# Line_Board.net
KiCad netlist of a schematic drawn in EAGLE
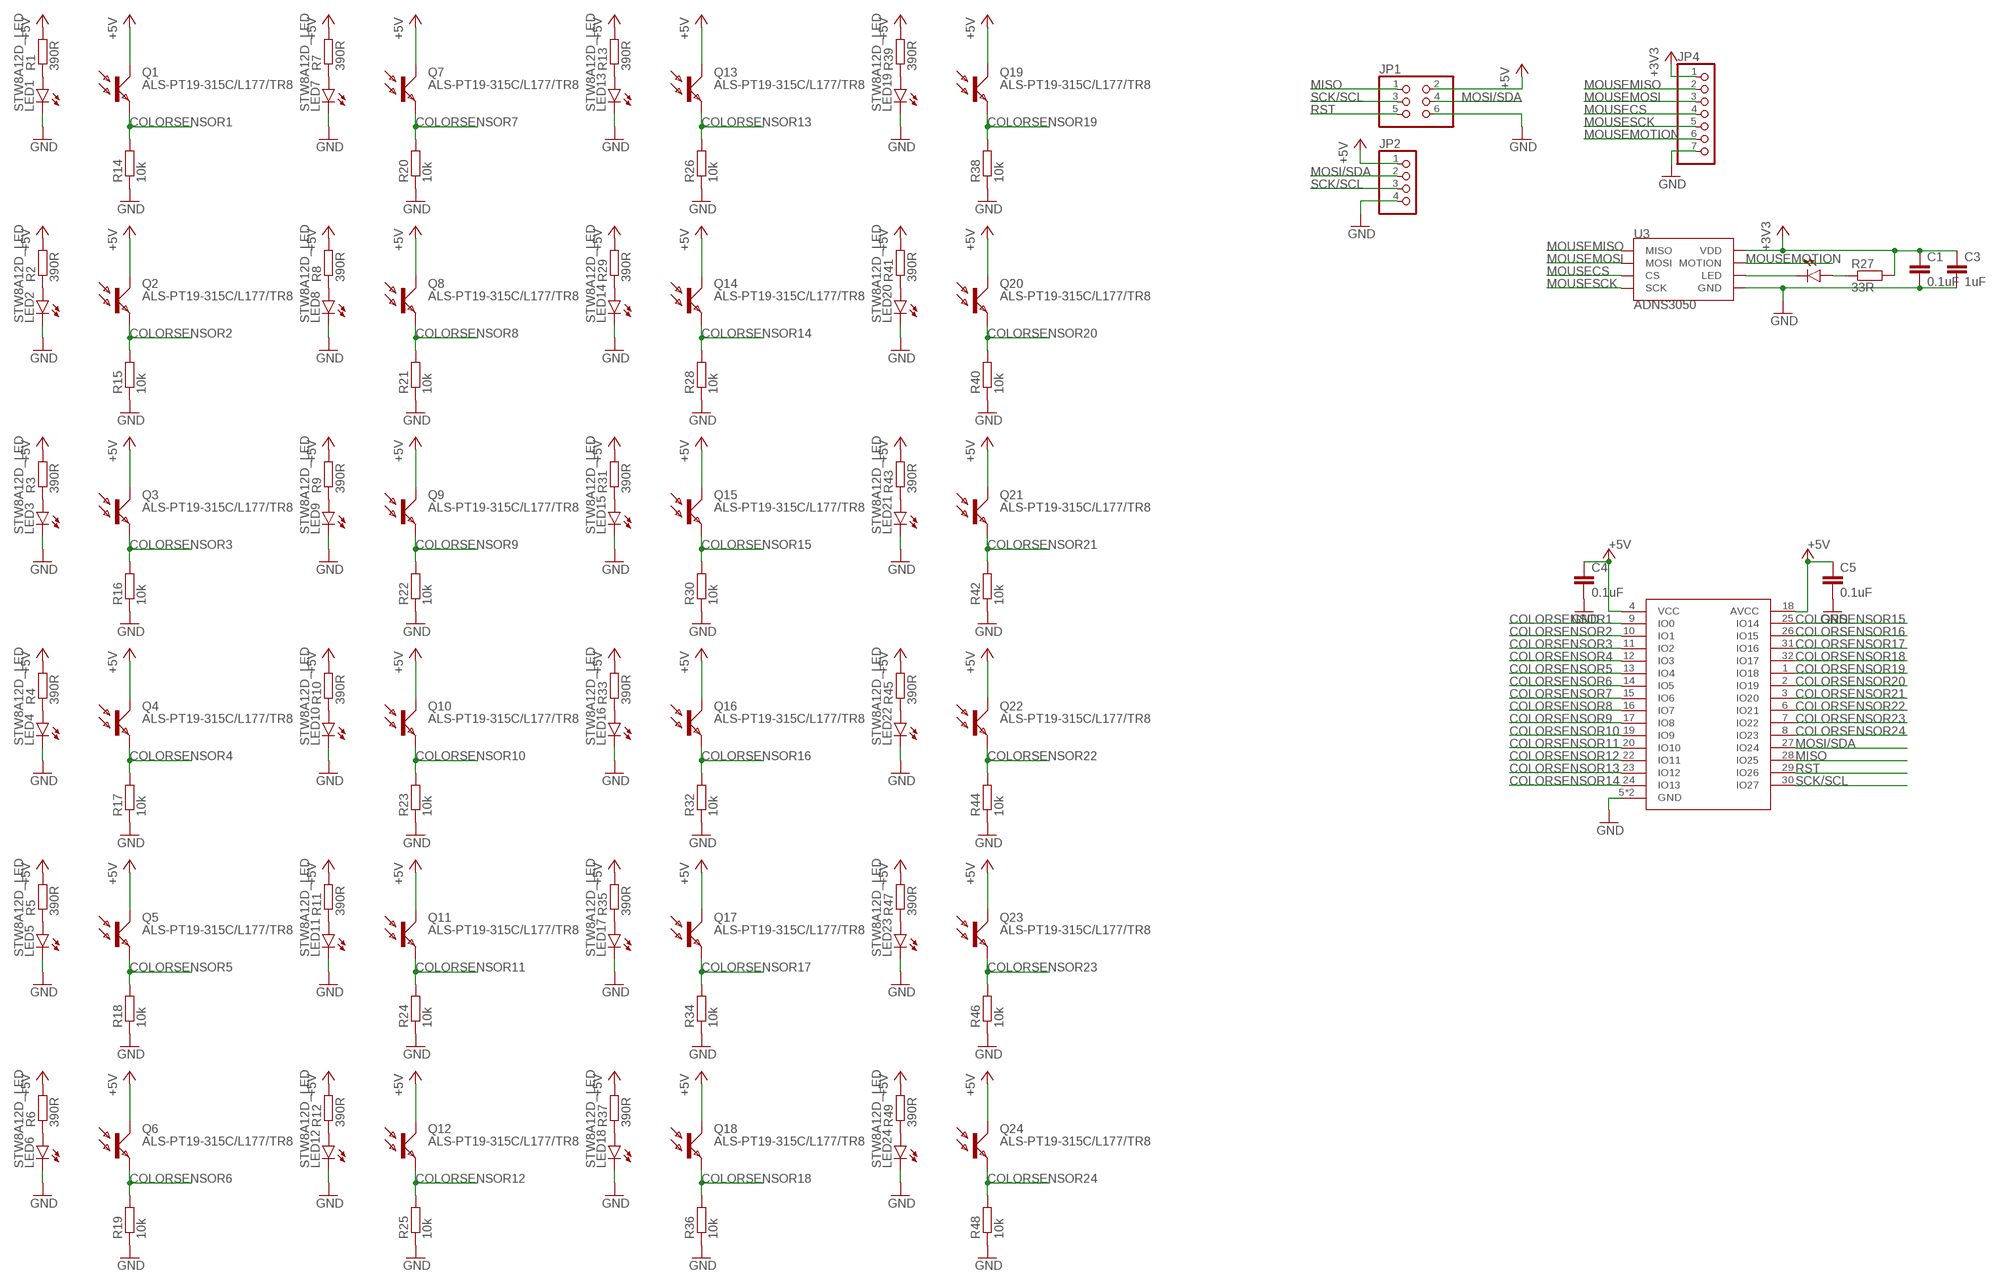
[diagram p0: schematic, sheet 1]

(export (version "E")
  (design (tool "Eeschema 10.0.6"))
  (components
    (comp (ref "C1")
      (value "0.1uF")
      (footprint "eagle-import:C0805")
      (libsource (lib "eagle-import") (part "C-EUC0805"))
    )
    (comp (ref "C3")
      (value "1uF")
      (footprint "eagle-import:C0805")
      (libsource (lib "eagle-import") (part "C-EUC0805"))
    )
    (comp (ref "C4")
      (value "0.1uF")
      (footprint "eagle-import:C0805")
      (libsource (lib "eagle-import") (part "C-EUC0805"))
    )
    (comp (ref "C5")
      (value "0.1uF")
      (footprint "eagle-import:C0805")
      (libsource (lib "eagle-import") (part "C-EUC0805"))
    )
    (comp (ref "JP1")
      (value "PINHD-2X3")
      (footprint "eagle-import:2X03")
      (libsource (lib "eagle-import") (part "PINHD-2X3"))
    )
    (comp (ref "JP2")
      (value "PINHD-1X4/90")
      (footprint "eagle-import:1X04_90")
      (libsource (lib "eagle-import") (part "PINHD-1X4/90"))
    )
    (comp (ref "JP4")
      (value "PINHD-1X7")
      (footprint "eagle-import:1X07")
      (libsource (lib "eagle-import") (part "PINHD-1X7"))
    )
    (comp (ref "LED1")
      (value "STW8A12D_LED")
      (footprint "eagle-import:LEDC3428X70")
      (libsource (lib "eagle-import") (part "STW8A12D_LED"))
    )
    (comp (ref "LED2")
      (value "STW8A12D_LED")
      (footprint "eagle-import:LEDC3428X70")
      (libsource (lib "eagle-import") (part "STW8A12D_LED"))
    )
    (comp (ref "LED3")
      (value "STW8A12D_LED")
      (footprint "eagle-import:LEDC3428X70")
      (libsource (lib "eagle-import") (part "STW8A12D_LED"))
    )
    (comp (ref "LED4")
      (value "STW8A12D_LED")
      (footprint "eagle-import:LEDC3428X70")
      (libsource (lib "eagle-import") (part "STW8A12D_LED"))
    )
    (comp (ref "LED5")
      (value "STW8A12D_LED")
      (footprint "eagle-import:LEDC3428X70")
      (libsource (lib "eagle-import") (part "STW8A12D_LED"))
    )
    (comp (ref "LED6")
      (value "STW8A12D_LED")
      (footprint "eagle-import:LEDC3428X70")
      (libsource (lib "eagle-import") (part "STW8A12D_LED"))
    )
    (comp (ref "LED7")
      (value "STW8A12D_LED")
      (footprint "eagle-import:LEDC3428X70")
      (libsource (lib "eagle-import") (part "STW8A12D_LED"))
    )
    (comp (ref "LED8")
      (value "STW8A12D_LED")
      (footprint "eagle-import:LEDC3428X70")
      (libsource (lib "eagle-import") (part "STW8A12D_LED"))
    )
    (comp (ref "LED9")
      (value "STW8A12D_LED")
      (footprint "eagle-import:LEDC3428X70")
      (libsource (lib "eagle-import") (part "STW8A12D_LED"))
    )
    (comp (ref "LED10")
      (value "STW8A12D_LED")
      (footprint "eagle-import:LEDC3428X70")
      (libsource (lib "eagle-import") (part "STW8A12D_LED"))
    )
    (comp (ref "LED11")
      (value "STW8A12D_LED")
      (footprint "eagle-import:LEDC3428X70")
      (libsource (lib "eagle-import") (part "STW8A12D_LED"))
    )
    (comp (ref "LED12")
      (value "STW8A12D_LED")
      (footprint "eagle-import:LEDC3428X70")
      (libsource (lib "eagle-import") (part "STW8A12D_LED"))
    )
    (comp (ref "LED13")
      (value "STW8A12D_LED")
      (footprint "eagle-import:LEDC3428X70")
      (libsource (lib "eagle-import") (part "STW8A12D_LED"))
    )
    (comp (ref "LED14")
      (value "STW8A12D_LED")
      (footprint "eagle-import:LEDC3428X70")
      (libsource (lib "eagle-import") (part "STW8A12D_LED"))
    )
    (comp (ref "LED15")
      (value "STW8A12D_LED")
      (footprint "eagle-import:LEDC3428X70")
      (libsource (lib "eagle-import") (part "STW8A12D_LED"))
    )
    (comp (ref "LED16")
      (value "STW8A12D_LED")
      (footprint "eagle-import:LEDC3428X70")
      (libsource (lib "eagle-import") (part "STW8A12D_LED"))
    )
    (comp (ref "LED17")
      (value "STW8A12D_LED")
      (footprint "eagle-import:LEDC3428X70")
      (libsource (lib "eagle-import") (part "STW8A12D_LED"))
    )
    (comp (ref "LED18")
      (value "STW8A12D_LED")
      (footprint "eagle-import:LEDC3428X70")
      (libsource (lib "eagle-import") (part "STW8A12D_LED"))
    )
    (comp (ref "LED19")
      (value "STW8A12D_LED")
      (footprint "eagle-import:LEDC3428X70")
      (libsource (lib "eagle-import") (part "STW8A12D_LED"))
    )
    (comp (ref "LED20")
      (value "STW8A12D_LED")
      (footprint "eagle-import:LEDC3428X70")
      (libsource (lib "eagle-import") (part "STW8A12D_LED"))
    )
    (comp (ref "LED21")
      (value "STW8A12D_LED")
      (footprint "eagle-import:LEDC3428X70")
      (libsource (lib "eagle-import") (part "STW8A12D_LED"))
    )
    (comp (ref "LED22")
      (value "STW8A12D_LED")
      (footprint "eagle-import:LEDC3428X70")
      (libsource (lib "eagle-import") (part "STW8A12D_LED"))
    )
    (comp (ref "LED23")
      (value "STW8A12D_LED")
      (footprint "eagle-import:LEDC3428X70")
      (libsource (lib "eagle-import") (part "STW8A12D_LED"))
    )
    (comp (ref "LED24")
      (value "STW8A12D_LED")
      (footprint "eagle-import:LEDC3428X70")
      (libsource (lib "eagle-import") (part "STW8A12D_LED"))
    )
    (comp (ref "Q1")
      (value "ALS-PT19-315C/L177/TR8")
      (footprint "eagle-import:LEDC1708X60")
      (libsource (lib "eagle-import") (part "ALS-PT19-315C/L177/TR8"))
    )
    (comp (ref "Q2")
      (value "ALS-PT19-315C/L177/TR8")
      (footprint "eagle-import:LEDC1708X60")
      (libsource (lib "eagle-import") (part "ALS-PT19-315C/L177/TR8"))
    )
    (comp (ref "Q3")
      (value "ALS-PT19-315C/L177/TR8")
      (footprint "eagle-import:LEDC1708X60")
      (libsource (lib "eagle-import") (part "ALS-PT19-315C/L177/TR8"))
    )
    (comp (ref "Q4")
      (value "ALS-PT19-315C/L177/TR8")
      (footprint "eagle-import:LEDC1708X60")
      (libsource (lib "eagle-import") (part "ALS-PT19-315C/L177/TR8"))
    )
    (comp (ref "Q5")
      (value "ALS-PT19-315C/L177/TR8")
      (footprint "eagle-import:LEDC1708X60")
      (libsource (lib "eagle-import") (part "ALS-PT19-315C/L177/TR8"))
    )
    (comp (ref "Q6")
      (value "ALS-PT19-315C/L177/TR8")
      (footprint "eagle-import:LEDC1708X60")
      (libsource (lib "eagle-import") (part "ALS-PT19-315C/L177/TR8"))
    )
    (comp (ref "Q7")
      (value "ALS-PT19-315C/L177/TR8")
      (footprint "eagle-import:LEDC1708X60")
      (libsource (lib "eagle-import") (part "ALS-PT19-315C/L177/TR8"))
    )
    (comp (ref "Q8")
      (value "ALS-PT19-315C/L177/TR8")
      (footprint "eagle-import:LEDC1708X60")
      (libsource (lib "eagle-import") (part "ALS-PT19-315C/L177/TR8"))
    )
    (comp (ref "Q9")
      (value "ALS-PT19-315C/L177/TR8")
      (footprint "eagle-import:LEDC1708X60")
      (libsource (lib "eagle-import") (part "ALS-PT19-315C/L177/TR8"))
    )
    (comp (ref "Q10")
      (value "ALS-PT19-315C/L177/TR8")
      (footprint "eagle-import:LEDC1708X60")
      (libsource (lib "eagle-import") (part "ALS-PT19-315C/L177/TR8"))
    )
    (comp (ref "Q11")
      (value "ALS-PT19-315C/L177/TR8")
      (footprint "eagle-import:LEDC1708X60")
      (libsource (lib "eagle-import") (part "ALS-PT19-315C/L177/TR8"))
    )
    (comp (ref "Q12")
      (value "ALS-PT19-315C/L177/TR8")
      (footprint "eagle-import:LEDC1708X60")
      (libsource (lib "eagle-import") (part "ALS-PT19-315C/L177/TR8"))
    )
    (comp (ref "Q13")
      (value "ALS-PT19-315C/L177/TR8")
      (footprint "eagle-import:LEDC1708X60")
      (libsource (lib "eagle-import") (part "ALS-PT19-315C/L177/TR8"))
    )
    (comp (ref "Q14")
      (value "ALS-PT19-315C/L177/TR8")
      (footprint "eagle-import:LEDC1708X60")
      (libsource (lib "eagle-import") (part "ALS-PT19-315C/L177/TR8"))
    )
    (comp (ref "Q15")
      (value "ALS-PT19-315C/L177/TR8")
      (footprint "eagle-import:LEDC1708X60")
      (libsource (lib "eagle-import") (part "ALS-PT19-315C/L177/TR8"))
    )
    (comp (ref "Q16")
      (value "ALS-PT19-315C/L177/TR8")
      (footprint "eagle-import:LEDC1708X60")
      (libsource (lib "eagle-import") (part "ALS-PT19-315C/L177/TR8"))
    )
    (comp (ref "Q17")
      (value "ALS-PT19-315C/L177/TR8")
      (footprint "eagle-import:LEDC1708X60")
      (libsource (lib "eagle-import") (part "ALS-PT19-315C/L177/TR8"))
    )
    (comp (ref "Q18")
      (value "ALS-PT19-315C/L177/TR8")
      (footprint "eagle-import:LEDC1708X60")
      (libsource (lib "eagle-import") (part "ALS-PT19-315C/L177/TR8"))
    )
    (comp (ref "Q19")
      (value "ALS-PT19-315C/L177/TR8")
      (footprint "eagle-import:LEDC1708X60")
      (libsource (lib "eagle-import") (part "ALS-PT19-315C/L177/TR8"))
    )
    (comp (ref "Q20")
      (value "ALS-PT19-315C/L177/TR8")
      (footprint "eagle-import:LEDC1708X60")
      (libsource (lib "eagle-import") (part "ALS-PT19-315C/L177/TR8"))
    )
    (comp (ref "Q21")
      (value "ALS-PT19-315C/L177/TR8")
      (footprint "eagle-import:LEDC1708X60")
      (libsource (lib "eagle-import") (part "ALS-PT19-315C/L177/TR8"))
    )
    (comp (ref "Q22")
      (value "ALS-PT19-315C/L177/TR8")
      (footprint "eagle-import:LEDC1708X60")
      (libsource (lib "eagle-import") (part "ALS-PT19-315C/L177/TR8"))
    )
    (comp (ref "Q23")
      (value "ALS-PT19-315C/L177/TR8")
      (footprint "eagle-import:LEDC1708X60")
      (libsource (lib "eagle-import") (part "ALS-PT19-315C/L177/TR8"))
    )
    (comp (ref "Q24")
      (value "ALS-PT19-315C/L177/TR8")
      (footprint "eagle-import:LEDC1708X60")
      (libsource (lib "eagle-import") (part "ALS-PT19-315C/L177/TR8"))
    )
    (comp (ref "R1")
      (value "390R")
      (footprint "eagle-import:R0805")
      (libsource (lib "eagle-import") (part "R-EU_R0805"))
    )
    (comp (ref "R2")
      (value "390R")
      (footprint "eagle-import:R0805")
      (libsource (lib "eagle-import") (part "R-EU_R0805"))
    )
    (comp (ref "R3")
      (value "390R")
      (footprint "eagle-import:R0805")
      (libsource (lib "eagle-import") (part "R-EU_R0805"))
    )
    (comp (ref "R4")
      (value "390R")
      (footprint "eagle-import:R0805")
      (libsource (lib "eagle-import") (part "R-EU_R0805"))
    )
    (comp (ref "R5")
      (value "390R")
      (footprint "eagle-import:R0805")
      (libsource (lib "eagle-import") (part "R-EU_R0805"))
    )
    (comp (ref "R6")
      (value "390R")
      (footprint "eagle-import:R0805")
      (libsource (lib "eagle-import") (part "R-EU_R0805"))
    )
    (comp (ref "R7")
      (value "390R")
      (footprint "eagle-import:R0805")
      (libsource (lib "eagle-import") (part "R-EU_R0805"))
    )
    (comp (ref "R8")
      (value "390R")
      (footprint "eagle-import:R0805")
      (libsource (lib "eagle-import") (part "R-EU_R0805"))
    )
    (comp (ref "R9")
      (value "390R")
      (footprint "eagle-import:R0805")
      (libsource (lib "eagle-import") (part "R-EU_R0805"))
    )
    (comp (ref "R10")
      (value "390R")
      (footprint "eagle-import:R0805")
      (libsource (lib "eagle-import") (part "R-EU_R0805"))
    )
    (comp (ref "R11")
      (value "390R")
      (footprint "eagle-import:R0805")
      (libsource (lib "eagle-import") (part "R-EU_R0805"))
    )
    (comp (ref "R12")
      (value "390R")
      (footprint "eagle-import:R0805")
      (libsource (lib "eagle-import") (part "R-EU_R0805"))
    )
    (comp (ref "R13")
      (value "390R")
      (footprint "eagle-import:R0805")
      (libsource (lib "eagle-import") (part "R-EU_R0805"))
    )
    (comp (ref "R14")
      (value "10k")
      (footprint "eagle-import:R0805")
      (libsource (lib "eagle-import") (part "R-EU_R0805"))
    )
    (comp (ref "R15")
      (value "10k")
      (footprint "eagle-import:R0805")
      (libsource (lib "eagle-import") (part "R-EU_R0805"))
    )
    (comp (ref "R16")
      (value "10k")
      (footprint "eagle-import:R0805")
      (libsource (lib "eagle-import") (part "R-EU_R0805"))
    )
    (comp (ref "R17")
      (value "10k")
      (footprint "eagle-import:R0805")
      (libsource (lib "eagle-import") (part "R-EU_R0805"))
    )
    (comp (ref "R18")
      (value "10k")
      (footprint "eagle-import:R0805")
      (libsource (lib "eagle-import") (part "R-EU_R0805"))
    )
    (comp (ref "R19")
      (value "10k")
      (footprint "eagle-import:R0805")
      (libsource (lib "eagle-import") (part "R-EU_R0805"))
    )
    (comp (ref "R20")
      (value "10k")
      (footprint "eagle-import:R0805")
      (libsource (lib "eagle-import") (part "R-EU_R0805"))
    )
    (comp (ref "R21")
      (value "10k")
      (footprint "eagle-import:R0805")
      (libsource (lib "eagle-import") (part "R-EU_R0805"))
    )
    (comp (ref "R22")
      (value "10k")
      (footprint "eagle-import:R0805")
      (libsource (lib "eagle-import") (part "R-EU_R0805"))
    )
    (comp (ref "R23")
      (value "10k")
      (footprint "eagle-import:R0805")
      (libsource (lib "eagle-import") (part "R-EU_R0805"))
    )
    (comp (ref "R24")
      (value "10k")
      (footprint "eagle-import:R0805")
      (libsource (lib "eagle-import") (part "R-EU_R0805"))
    )
    (comp (ref "R25")
      (value "10k")
      (footprint "eagle-import:R0805")
      (libsource (lib "eagle-import") (part "R-EU_R0805"))
    )
    (comp (ref "R26")
      (value "10k")
      (footprint "eagle-import:R0805")
      (libsource (lib "eagle-import") (part "R-EU_R0805"))
    )
    (comp (ref "R27")
      (value "33R")
      (footprint "eagle-import:R0805")
      (libsource (lib "eagle-import") (part "R-EU_R0805"))
    )
    (comp (ref "R28")
      (value "10k")
      (footprint "eagle-import:R0805")
      (libsource (lib "eagle-import") (part "R-EU_R0805"))
    )
    (comp (ref "R29")
      (value "390R")
      (footprint "eagle-import:R0805")
      (libsource (lib "eagle-import") (part "R-EU_R0805"))
    )
    (comp (ref "R30")
      (value "10k")
      (footprint "eagle-import:R0805")
      (libsource (lib "eagle-import") (part "R-EU_R0805"))
    )
    (comp (ref "R31")
      (value "390R")
      (footprint "eagle-import:R0805")
      (libsource (lib "eagle-import") (part "R-EU_R0805"))
    )
    (comp (ref "R32")
      (value "10k")
      (footprint "eagle-import:R0805")
      (libsource (lib "eagle-import") (part "R-EU_R0805"))
    )
    (comp (ref "R33")
      (value "390R")
      (footprint "eagle-import:R0805")
      (libsource (lib "eagle-import") (part "R-EU_R0805"))
    )
    (comp (ref "R34")
      (value "10k")
      (footprint "eagle-import:R0805")
      (libsource (lib "eagle-import") (part "R-EU_R0805"))
    )
    (comp (ref "R35")
      (value "390R")
      (footprint "eagle-import:R0805")
      (libsource (lib "eagle-import") (part "R-EU_R0805"))
    )
    (comp (ref "R36")
      (value "10k")
      (footprint "eagle-import:R0805")
      (libsource (lib "eagle-import") (part "R-EU_R0805"))
    )
    (comp (ref "R37")
      (value "390R")
      (footprint "eagle-import:R0805")
      (libsource (lib "eagle-import") (part "R-EU_R0805"))
    )
    (comp (ref "R38")
      (value "10k")
      (footprint "eagle-import:R0805")
      (libsource (lib "eagle-import") (part "R-EU_R0805"))
    )
    (comp (ref "R39")
      (value "390R")
      (footprint "eagle-import:R0805")
      (libsource (lib "eagle-import") (part "R-EU_R0805"))
    )
    (comp (ref "R40")
      (value "10k")
      (footprint "eagle-import:R0805")
      (libsource (lib "eagle-import") (part "R-EU_R0805"))
    )
    (comp (ref "R41")
      (value "390R")
      (footprint "eagle-import:R0805")
      (libsource (lib "eagle-import") (part "R-EU_R0805"))
    )
    (comp (ref "R42")
      (value "10k")
      (footprint "eagle-import:R0805")
      (libsource (lib "eagle-import") (part "R-EU_R0805"))
    )
    (comp (ref "R43")
      (value "390R")
      (footprint "eagle-import:R0805")
      (libsource (lib "eagle-import") (part "R-EU_R0805"))
    )
    (comp (ref "R44")
      (value "10k")
      (footprint "eagle-import:R0805")
      (libsource (lib "eagle-import") (part "R-EU_R0805"))
    )
    (comp (ref "R45")
      (value "390R")
      (footprint "eagle-import:R0805")
      (libsource (lib "eagle-import") (part "R-EU_R0805"))
    )
    (comp (ref "R46")
      (value "10k")
      (footprint "eagle-import:R0805")
      (libsource (lib "eagle-import") (part "R-EU_R0805"))
    )
    (comp (ref "R47")
      (value "390R")
      (footprint "eagle-import:R0805")
      (libsource (lib "eagle-import") (part "R-EU_R0805"))
    )
    (comp (ref "R48")
      (value "10k")
      (footprint "eagle-import:R0805")
      (libsource (lib "eagle-import") (part "R-EU_R0805"))
    )
    (comp (ref "R49")
      (value "390R")
      (footprint "eagle-import:R0805")
      (libsource (lib "eagle-import") (part "R-EU_R0805"))
    )
    (comp (ref "U2")
      (value "ATTINY828")
      (footprint "eagle-import:QFP80P900X900X120-32")
      (libsource (lib "eagle-import") (part "ATTINY828"))
    )
    (comp (ref "U3")
      (value "ADNS3050")
      (footprint "eagle-import:ADNS3050")
      (libsource (lib "eagle-import") (part "ADNS3050"))
    )
  )
  (nets
    (net (code "1") (name "+3V3") (class "Default")
      (node (ref "C1") (pin "1") (pinfunction "1_1") (pintype "passive"))
      (node (ref "C3") (pin "1") (pinfunction "1_1") (pintype "passive"))
      (node (ref "JP4") (pin "1") (pinfunction "1_1") (pintype "passive"))
      (node (ref "R27") (pin "2") (pinfunction "2_2") (pintype "passive"))
      (node (ref "U3") (pin "7") (pinfunction "VDD_7") (pintype "power_in"))
    )
    (net (code "2") (name "+5V") (class "Default")
      (node (ref "C4") (pin "1") (pinfunction "1_1") (pintype "passive"))
      (node (ref "C5") (pin "1") (pinfunction "1_1") (pintype "passive"))
      (node (ref "JP1") (pin "2") (pinfunction "2_2") (pintype "passive"))
      (node (ref "JP2") (pin "1") (pinfunction "1_1") (pintype "passive"))
      (node (ref "Q1") (pin "C") (pinfunction "C_C") (pintype "passive"))
      (node (ref "Q10") (pin "C") (pinfunction "C_C") (pintype "passive"))
      (node (ref "Q11") (pin "C") (pinfunction "C_C") (pintype "passive"))
      (node (ref "Q12") (pin "C") (pinfunction "C_C") (pintype "passive"))
      (node (ref "Q13") (pin "C") (pinfunction "C_C") (pintype "passive"))
      (node (ref "Q14") (pin "C") (pinfunction "C_C") (pintype "passive"))
      (node (ref "Q15") (pin "C") (pinfunction "C_C") (pintype "passive"))
      (node (ref "Q16") (pin "C") (pinfunction "C_C") (pintype "passive"))
      (node (ref "Q17") (pin "C") (pinfunction "C_C") (pintype "passive"))
      (node (ref "Q18") (pin "C") (pinfunction "C_C") (pintype "passive"))
      (node (ref "Q19") (pin "C") (pinfunction "C_C") (pintype "passive"))
      (node (ref "Q2") (pin "C") (pinfunction "C_C") (pintype "passive"))
      (node (ref "Q20") (pin "C") (pinfunction "C_C") (pintype "passive"))
      (node (ref "Q21") (pin "C") (pinfunction "C_C") (pintype "passive"))
      (node (ref "Q22") (pin "C") (pinfunction "C_C") (pintype "passive"))
      (node (ref "Q23") (pin "C") (pinfunction "C_C") (pintype "passive"))
      (node (ref "Q24") (pin "C") (pinfunction "C_C") (pintype "passive"))
      (node (ref "Q3") (pin "C") (pinfunction "C_C") (pintype "passive"))
      (node (ref "Q4") (pin "C") (pinfunction "C_C") (pintype "passive"))
      (node (ref "Q5") (pin "C") (pinfunction "C_C") (pintype "passive"))
      (node (ref "Q6") (pin "C") (pinfunction "C_C") (pintype "passive"))
      (node (ref "Q7") (pin "C") (pinfunction "C_C") (pintype "passive"))
      (node (ref "Q8") (pin "C") (pinfunction "C_C") (pintype "passive"))
      (node (ref "Q9") (pin "C") (pinfunction "C_C") (pintype "passive"))
      (node (ref "R1") (pin "2") (pinfunction "2_2") (pintype "passive"))
      (node (ref "R10") (pin "2") (pinfunction "2_2") (pintype "passive"))
      (node (ref "R11") (pin "2") (pinfunction "2_2") (pintype "passive"))
      (node (ref "R12") (pin "2") (pinfunction "2_2") (pintype "passive"))
      (node (ref "R13") (pin "2") (pinfunction "2_2") (pintype "passive"))
      (node (ref "R2") (pin "2") (pinfunction "2_2") (pintype "passive"))
      (node (ref "R29") (pin "2") (pinfunction "2_2") (pintype "passive"))
      (node (ref "R3") (pin "2") (pinfunction "2_2") (pintype "passive"))
      (node (ref "R31") (pin "2") (pinfunction "2_2") (pintype "passive"))
      (node (ref "R33") (pin "2") (pinfunction "2_2") (pintype "passive"))
      (node (ref "R35") (pin "2") (pinfunction "2_2") (pintype "passive"))
      (node (ref "R37") (pin "2") (pinfunction "2_2") (pintype "passive"))
      (node (ref "R39") (pin "2") (pinfunction "2_2") (pintype "passive"))
      (node (ref "R4") (pin "2") (pinfunction "2_2") (pintype "passive"))
      (node (ref "R41") (pin "2") (pinfunction "2_2") (pintype "passive"))
      (node (ref "R43") (pin "2") (pinfunction "2_2") (pintype "passive"))
      (node (ref "R45") (pin "2") (pinfunction "2_2") (pintype "passive"))
      (node (ref "R47") (pin "2") (pinfunction "2_2") (pintype "passive"))
      (node (ref "R49") (pin "2") (pinfunction "2_2") (pintype "passive"))
      (node (ref "R5") (pin "2") (pinfunction "2_2") (pintype "passive"))
      (node (ref "R6") (pin "2") (pinfunction "2_2") (pintype "passive"))
      (node (ref "R7") (pin "2") (pinfunction "2_2") (pintype "passive"))
      (node (ref "R8") (pin "2") (pinfunction "2_2") (pintype "passive"))
      (node (ref "R9") (pin "2") (pinfunction "2_2") (pintype "passive"))
      (node (ref "U2") (pin "18") (pinfunction "AVCC_18") (pintype "power_in"))
      (node (ref "U2") (pin "4") (pinfunction "VCC_4") (pintype "power_in"))
    )
    (net (code "3") (name "/COLORSENSOR1") (class "Default")
      (node (ref "Q1") (pin "E") (pinfunction "E_E") (pintype "passive"))
      (node (ref "R14") (pin "2") (pinfunction "2_2") (pintype "passive"))
      (node (ref "U2") (pin "9") (pinfunction "IO0_9") (pintype "bidirectional"))
    )
    (net (code "4") (name "/COLORSENSOR2") (class "Default")
      (node (ref "Q2") (pin "E") (pinfunction "E_E") (pintype "passive"))
      (node (ref "R15") (pin "2") (pinfunction "2_2") (pintype "passive"))
      (node (ref "U2") (pin "10") (pinfunction "IO1_10") (pintype "bidirectional"))
    )
    (net (code "5") (name "/COLORSENSOR3") (class "Default")
      (node (ref "Q3") (pin "E") (pinfunction "E_E") (pintype "passive"))
      (node (ref "R16") (pin "2") (pinfunction "2_2") (pintype "passive"))
      (node (ref "U2") (pin "11") (pinfunction "IO2_11") (pintype "bidirectional"))
    )
    (net (code "6") (name "/COLORSENSOR4") (class "Default")
      (node (ref "Q4") (pin "E") (pinfunction "E_E") (pintype "passive"))
      (node (ref "R17") (pin "2") (pinfunction "2_2") (pintype "passive"))
      (node (ref "U2") (pin "12") (pinfunction "IO3_12") (pintype "bidirectional"))
    )
    (net (code "7") (name "/COLORSENSOR5") (class "Default")
      (node (ref "Q5") (pin "E") (pinfunction "E_E") (pintype "passive"))
      (node (ref "R18") (pin "2") (pinfunction "2_2") (pintype "passive"))
      (node (ref "U2") (pin "13") (pinfunction "IO4_13") (pintype "bidirectional"))
    )
    (net (code "8") (name "/COLORSENSOR6") (class "Default")
      (node (ref "Q6") (pin "E") (pinfunction "E_E") (pintype "passive"))
      (node (ref "R19") (pin "2") (pinfunction "2_2") (pintype "passive"))
      (node (ref "U2") (pin "14") (pinfunction "IO5_14") (pintype "bidirectional"))
    )
    (net (code "9") (name "/COLORSENSOR7") (class "Default")
      (node (ref "Q7") (pin "E") (pinfunction "E_E") (pintype "passive"))
      (node (ref "R20") (pin "2") (pinfunction "2_2") (pintype "passive"))
      (node (ref "U2") (pin "15") (pinfunction "IO6_15") (pintype "bidirectional"))
    )
    (net (code "10") (name "/COLORSENSOR8") (class "Default")
      (node (ref "Q8") (pin "E") (pinfunction "E_E") (pintype "passive"))
      (node (ref "R21") (pin "2") (pinfunction "2_2") (pintype "passive"))
      (node (ref "U2") (pin "16") (pinfunction "IO7_16") (pintype "bidirectional"))
    )
    (net (code "11") (name "/COLORSENSOR9") (class "Default")
      (node (ref "Q9") (pin "E") (pinfunction "E_E") (pintype "passive"))
      (node (ref "R22") (pin "2") (pinfunction "2_2") (pintype "passive"))
      (node (ref "U2") (pin "17") (pinfunction "IO8_17") (pintype "bidirectional"))
    )
    (net (code "12") (name "/COLORSENSOR10") (class "Default")
      (node (ref "Q10") (pin "E") (pinfunction "E_E") (pintype "passive"))
      (node (ref "R23") (pin "2") (pinfunction "2_2") (pintype "passive"))
      (node (ref "U2") (pin "19") (pinfunction "IO9_19") (pintype "bidirectional"))
    )
    (net (code "13") (name "/COLORSENSOR11") (class "Default")
      (node (ref "Q11") (pin "E") (pinfunction "E_E") (pintype "passive"))
      (node (ref "R24") (pin "2") (pinfunction "2_2") (pintype "passive"))
      (node (ref "U2") (pin "20") (pinfunction "IO10_20") (pintype "bidirectional"))
    )
    (net (code "14") (name "/COLORSENSOR12") (class "Default")
      (node (ref "Q12") (pin "E") (pinfunction "E_E") (pintype "passive"))
      (node (ref "R25") (pin "2") (pinfunction "2_2") (pintype "passive"))
      (node (ref "U2") (pin "22") (pinfunction "IO11_22") (pintype "bidirectional"))
    )
    (net (code "15") (name "/COLORSENSOR13") (class "Default")
      (node (ref "Q13") (pin "E") (pinfunction "E_E") (pintype "passive"))
      (node (ref "R26") (pin "2") (pinfunction "2_2") (pintype "passive"))
      (node (ref "U2") (pin "23") (pinfunction "IO12_23") (pintype "bidirectional"))
    )
    (net (code "16") (name "/COLORSENSOR14") (class "Default")
      (node (ref "Q14") (pin "E") (pinfunction "E_E") (pintype "passive"))
      (node (ref "R28") (pin "2") (pinfunction "2_2") (pintype "passive"))
      (node (ref "U2") (pin "24") (pinfunction "IO13_24") (pintype "bidirectional"))
    )
    (net (code "17") (name "/COLORSENSOR15") (class "Default")
      (node (ref "Q15") (pin "E") (pinfunction "E_E") (pintype "passive"))
      (node (ref "R30") (pin "2") (pinfunction "2_2") (pintype "passive"))
      (node (ref "U2") (pin "25") (pinfunction "IO14_25") (pintype "bidirectional"))
    )
    (net (code "18") (name "/COLORSENSOR16") (class "Default")
      (node (ref "Q16") (pin "E") (pinfunction "E_E") (pintype "passive"))
      (node (ref "R32") (pin "2") (pinfunction "2_2") (pintype "passive"))
      (node (ref "U2") (pin "26") (pinfunction "IO15_26") (pintype "bidirectional"))
    )
    (net (code "19") (name "/COLORSENSOR17") (class "Default")
      (node (ref "Q17") (pin "E") (pinfunction "E_E") (pintype "passive"))
      (node (ref "R34") (pin "2") (pinfunction "2_2") (pintype "passive"))
      (node (ref "U2") (pin "31") (pinfunction "IO16_31") (pintype "bidirectional"))
    )
    (net (code "20") (name "/COLORSENSOR18") (class "Default")
      (node (ref "Q18") (pin "E") (pinfunction "E_E") (pintype "passive"))
      (node (ref "R36") (pin "2") (pinfunction "2_2") (pintype "passive"))
      (node (ref "U2") (pin "32") (pinfunction "IO17_32") (pintype "bidirectional"))
    )
    (net (code "21") (name "/COLORSENSOR19") (class "Default")
      (node (ref "Q19") (pin "E") (pinfunction "E_E") (pintype "passive"))
      (node (ref "R38") (pin "2") (pinfunction "2_2") (pintype "passive"))
      (node (ref "U2") (pin "1") (pinfunction "IO18_1") (pintype "bidirectional"))
    )
    (net (code "22") (name "/COLORSENSOR20") (class "Default")
      (node (ref "Q20") (pin "E") (pinfunction "E_E") (pintype "passive"))
      (node (ref "R40") (pin "2") (pinfunction "2_2") (pintype "passive"))
      (node (ref "U2") (pin "2") (pinfunction "IO19_2") (pintype "bidirectional"))
    )
    (net (code "23") (name "/COLORSENSOR21") (class "Default")
      (node (ref "Q21") (pin "E") (pinfunction "E_E") (pintype "passive"))
      (node (ref "R42") (pin "2") (pinfunction "2_2") (pintype "passive"))
      (node (ref "U2") (pin "3") (pinfunction "IO20_3") (pintype "bidirectional"))
    )
    (net (code "24") (name "/COLORSENSOR22") (class "Default")
      (node (ref "Q22") (pin "E") (pinfunction "E_E") (pintype "passive"))
      (node (ref "R44") (pin "2") (pinfunction "2_2") (pintype "passive"))
      (node (ref "U2") (pin "6") (pinfunction "IO21_6") (pintype "bidirectional"))
    )
    (net (code "25") (name "/COLORSENSOR23") (class "Default")
      (node (ref "Q23") (pin "E") (pinfunction "E_E") (pintype "passive"))
      (node (ref "R46") (pin "2") (pinfunction "2_2") (pintype "passive"))
      (node (ref "U2") (pin "7") (pinfunction "IO22_7") (pintype "bidirectional"))
    )
    (net (code "26") (name "/COLORSENSOR24") (class "Default")
      (node (ref "Q24") (pin "E") (pinfunction "E_E") (pintype "passive"))
      (node (ref "R48") (pin "2") (pinfunction "2_2") (pintype "passive"))
      (node (ref "U2") (pin "8") (pinfunction "IO23_8") (pintype "bidirectional"))
    )
    (net (code "27") (name "/MISO") (class "Default")
      (node (ref "JP1") (pin "1") (pinfunction "1_1") (pintype "passive"))
      (node (ref "U2") (pin "28") (pinfunction "IO25_28") (pintype "bidirectional"))
    )
    (net (code "28") (name "/MOSI{slash}SDA") (class "Default")
      (node (ref "JP1") (pin "4") (pinfunction "4_4") (pintype "passive"))
      (node (ref "JP2") (pin "2") (pinfunction "2_2") (pintype "passive"))
      (node (ref "U2") (pin "27") (pinfunction "IO24_27") (pintype "bidirectional"))
    )
    (net (code "29") (name "/MOUSECS") (class "Default")
      (node (ref "JP4") (pin "4") (pinfunction "4_4") (pintype "passive"))
      (node (ref "U3") (pin "4") (pinfunction "CS_4") (pintype "bidirectional"))
    )
    (net (code "30") (name "/MOUSEMISO") (class "Default")
      (node (ref "JP4") (pin "2") (pinfunction "2_2") (pintype "passive"))
      (node (ref "U3") (pin "1") (pinfunction "MISO_1") (pintype "bidirectional"))
    )
    (net (code "31") (name "/MOUSEMOSI") (class "Default")
      (node (ref "JP4") (pin "3") (pinfunction "3_3") (pintype "passive"))
      (node (ref "U3") (pin "3") (pinfunction "MOSI_3") (pintype "bidirectional"))
    )
    (net (code "32") (name "/MOUSEMOTION") (class "Default")
      (node (ref "JP4") (pin "6") (pinfunction "6_6") (pintype "passive"))
      (node (ref "U3") (pin "8") (pinfunction "MOTION_8") (pintype "output"))
    )
    (net (code "33") (name "/MOUSESCK") (class "Default")
      (node (ref "JP4") (pin "5") (pinfunction "5_5") (pintype "passive"))
      (node (ref "U3") (pin "5") (pinfunction "SCK_5") (pintype "bidirectional"))
    )
    (net (code "34") (name "/RST") (class "Default")
      (node (ref "JP1") (pin "5") (pinfunction "5_5") (pintype "passive"))
      (node (ref "U2") (pin "29") (pinfunction "IO26_29") (pintype "bidirectional"))
    )
    (net (code "35") (name "/SCK{slash}SCL") (class "Default")
      (node (ref "JP1") (pin "3") (pinfunction "3_3") (pintype "passive"))
      (node (ref "JP2") (pin "3") (pinfunction "3_3") (pintype "passive"))
      (node (ref "U2") (pin "30") (pinfunction "IO27_30") (pintype "bidirectional"))
    )
    (net (code "36") (name "GND") (class "Default")
      (node (ref "C1") (pin "2") (pinfunction "2_2") (pintype "passive"))
      (node (ref "C3") (pin "2") (pinfunction "2_2") (pintype "passive"))
      (node (ref "C4") (pin "2") (pinfunction "2_2") (pintype "passive"))
      (node (ref "C5") (pin "2") (pinfunction "2_2") (pintype "passive"))
      (node (ref "JP1") (pin "6") (pinfunction "6_6") (pintype "passive"))
      (node (ref "JP2") (pin "4") (pinfunction "4_4") (pintype "passive"))
      (node (ref "JP4") (pin "7") (pinfunction "7_7") (pintype "passive"))
      (node (ref "LED1") (pin "2") (pinfunction "C_2") (pintype "passive"))
      (node (ref "LED10") (pin "2") (pinfunction "C_2") (pintype "passive"))
      (node (ref "LED11") (pin "2") (pinfunction "C_2") (pintype "passive"))
      (node (ref "LED12") (pin "2") (pinfunction "C_2") (pintype "passive"))
      (node (ref "LED13") (pin "2") (pinfunction "C_2") (pintype "passive"))
      (node (ref "LED14") (pin "2") (pinfunction "C_2") (pintype "passive"))
      (node (ref "LED15") (pin "2") (pinfunction "C_2") (pintype "passive"))
      (node (ref "LED16") (pin "2") (pinfunction "C_2") (pintype "passive"))
      (node (ref "LED17") (pin "2") (pinfunction "C_2") (pintype "passive"))
      (node (ref "LED18") (pin "2") (pinfunction "C_2") (pintype "passive"))
      (node (ref "LED19") (pin "2") (pinfunction "C_2") (pintype "passive"))
      (node (ref "LED2") (pin "2") (pinfunction "C_2") (pintype "passive"))
      (node (ref "LED20") (pin "2") (pinfunction "C_2") (pintype "passive"))
      (node (ref "LED21") (pin "2") (pinfunction "C_2") (pintype "passive"))
      (node (ref "LED22") (pin "2") (pinfunction "C_2") (pintype "passive"))
      (node (ref "LED23") (pin "2") (pinfunction "C_2") (pintype "passive"))
      (node (ref "LED24") (pin "2") (pinfunction "C_2") (pintype "passive"))
      (node (ref "LED3") (pin "2") (pinfunction "C_2") (pintype "passive"))
      (node (ref "LED4") (pin "2") (pinfunction "C_2") (pintype "passive"))
      (node (ref "LED5") (pin "2") (pinfunction "C_2") (pintype "passive"))
      (node (ref "LED6") (pin "2") (pinfunction "C_2") (pintype "passive"))
      (node (ref "LED7") (pin "2") (pinfunction "C_2") (pintype "passive"))
      (node (ref "LED8") (pin "2") (pinfunction "C_2") (pintype "passive"))
      (node (ref "LED9") (pin "2") (pinfunction "C_2") (pintype "passive"))
      (node (ref "R14") (pin "1") (pinfunction "1_1") (pintype "passive"))
      (node (ref "R15") (pin "1") (pinfunction "1_1") (pintype "passive"))
      (node (ref "R16") (pin "1") (pinfunction "1_1") (pintype "passive"))
      (node (ref "R17") (pin "1") (pinfunction "1_1") (pintype "passive"))
      (node (ref "R18") (pin "1") (pinfunction "1_1") (pintype "passive"))
      (node (ref "R19") (pin "1") (pinfunction "1_1") (pintype "passive"))
      (node (ref "R20") (pin "1") (pinfunction "1_1") (pintype "passive"))
      (node (ref "R21") (pin "1") (pinfunction "1_1") (pintype "passive"))
      (node (ref "R22") (pin "1") (pinfunction "1_1") (pintype "passive"))
      (node (ref "R23") (pin "1") (pinfunction "1_1") (pintype "passive"))
      (node (ref "R24") (pin "1") (pinfunction "1_1") (pintype "passive"))
      (node (ref "R25") (pin "1") (pinfunction "1_1") (pintype "passive"))
      (node (ref "R26") (pin "1") (pinfunction "1_1") (pintype "passive"))
      (node (ref "R28") (pin "1") (pinfunction "1_1") (pintype "passive"))
      (node (ref "R30") (pin "1") (pinfunction "1_1") (pintype "passive"))
      (node (ref "R32") (pin "1") (pinfunction "1_1") (pintype "passive"))
      (node (ref "R34") (pin "1") (pinfunction "1_1") (pintype "passive"))
      (node (ref "R36") (pin "1") (pinfunction "1_1") (pintype "passive"))
      (node (ref "R38") (pin "1") (pinfunction "1_1") (pintype "passive"))
      (node (ref "R40") (pin "1") (pinfunction "1_1") (pintype "passive"))
      (node (ref "R42") (pin "1") (pinfunction "1_1") (pintype "passive"))
      (node (ref "R44") (pin "1") (pinfunction "1_1") (pintype "passive"))
      (node (ref "R46") (pin "1") (pinfunction "1_1") (pintype "passive"))
      (node (ref "R48") (pin "1") (pinfunction "1_1") (pintype "passive"))
      (node (ref "U2") (pin "21") (pinfunction "GND_21") (pintype "power_in"))
      (node (ref "U2") (pin "5") (pinfunction "GND_5") (pintype "power_in"))
      (node (ref "U3") (pin "6") (pinfunction "GND_6") (pintype "power_in"))
    )
    (net (code "37") (name "Net-(LED1-A)") (class "Default")
      (node (ref "LED1") (pin "1") (pinfunction "A_1") (pintype "passive"))
      (node (ref "R1") (pin "1") (pinfunction "1_1") (pintype "passive"))
    )
    (net (code "38") (name "Net-(LED2-A)") (class "Default")
      (node (ref "LED2") (pin "1") (pinfunction "A_1") (pintype "passive"))
      (node (ref "R2") (pin "1") (pinfunction "1_1") (pintype "passive"))
    )
    (net (code "39") (name "Net-(LED3-A)") (class "Default")
      (node (ref "LED3") (pin "1") (pinfunction "A_1") (pintype "passive"))
      (node (ref "R3") (pin "1") (pinfunction "1_1") (pintype "passive"))
    )
    (net (code "40") (name "Net-(LED4-A)") (class "Default")
      (node (ref "LED4") (pin "1") (pinfunction "A_1") (pintype "passive"))
      (node (ref "R4") (pin "1") (pinfunction "1_1") (pintype "passive"))
    )
    (net (code "41") (name "Net-(LED5-A)") (class "Default")
      (node (ref "LED5") (pin "1") (pinfunction "A_1") (pintype "passive"))
      (node (ref "R5") (pin "1") (pinfunction "1_1") (pintype "passive"))
    )
    (net (code "42") (name "Net-(LED6-A)") (class "Default")
      (node (ref "LED6") (pin "1") (pinfunction "A_1") (pintype "passive"))
      (node (ref "R6") (pin "1") (pinfunction "1_1") (pintype "passive"))
    )
    (net (code "43") (name "Net-(LED7-A)") (class "Default")
      (node (ref "LED7") (pin "1") (pinfunction "A_1") (pintype "passive"))
      (node (ref "R7") (pin "1") (pinfunction "1_1") (pintype "passive"))
    )
    (net (code "44") (name "Net-(LED8-A)") (class "Default")
      (node (ref "LED8") (pin "1") (pinfunction "A_1") (pintype "passive"))
      (node (ref "R8") (pin "1") (pinfunction "1_1") (pintype "passive"))
    )
    (net (code "45") (name "Net-(LED9-A)") (class "Default")
      (node (ref "LED9") (pin "1") (pinfunction "A_1") (pintype "passive"))
      (node (ref "R9") (pin "1") (pinfunction "1_1") (pintype "passive"))
    )
    (net (code "46") (name "Net-(LED10-A)") (class "Default")
      (node (ref "LED10") (pin "1") (pinfunction "A_1") (pintype "passive"))
      (node (ref "R10") (pin "1") (pinfunction "1_1") (pintype "passive"))
    )
    (net (code "47") (name "Net-(LED11-A)") (class "Default")
      (node (ref "LED11") (pin "1") (pinfunction "A_1") (pintype "passive"))
      (node (ref "R11") (pin "1") (pinfunction "1_1") (pintype "passive"))
    )
    (net (code "48") (name "Net-(LED12-A)") (class "Default")
      (node (ref "LED12") (pin "1") (pinfunction "A_1") (pintype "passive"))
      (node (ref "R12") (pin "1") (pinfunction "1_1") (pintype "passive"))
    )
    (net (code "49") (name "Net-(LED13-A)") (class "Default")
      (node (ref "LED13") (pin "1") (pinfunction "A_1") (pintype "passive"))
      (node (ref "R13") (pin "1") (pinfunction "1_1") (pintype "passive"))
    )
    (net (code "50") (name "Net-(LED14-A)") (class "Default")
      (node (ref "LED14") (pin "1") (pinfunction "A_1") (pintype "passive"))
      (node (ref "R29") (pin "1") (pinfunction "1_1") (pintype "passive"))
    )
    (net (code "51") (name "Net-(LED15-A)") (class "Default")
      (node (ref "LED15") (pin "1") (pinfunction "A_1") (pintype "passive"))
      (node (ref "R31") (pin "1") (pinfunction "1_1") (pintype "passive"))
    )
    (net (code "52") (name "Net-(LED16-A)") (class "Default")
      (node (ref "LED16") (pin "1") (pinfunction "A_1") (pintype "passive"))
      (node (ref "R33") (pin "1") (pinfunction "1_1") (pintype "passive"))
    )
    (net (code "53") (name "Net-(LED17-A)") (class "Default")
      (node (ref "LED17") (pin "1") (pinfunction "A_1") (pintype "passive"))
      (node (ref "R35") (pin "1") (pinfunction "1_1") (pintype "passive"))
    )
    (net (code "54") (name "Net-(LED18-A)") (class "Default")
      (node (ref "LED18") (pin "1") (pinfunction "A_1") (pintype "passive"))
      (node (ref "R37") (pin "1") (pinfunction "1_1") (pintype "passive"))
    )
    (net (code "55") (name "Net-(LED19-A)") (class "Default")
      (node (ref "LED19") (pin "1") (pinfunction "A_1") (pintype "passive"))
      (node (ref "R39") (pin "1") (pinfunction "1_1") (pintype "passive"))
    )
    (net (code "56") (name "Net-(LED20-A)") (class "Default")
      (node (ref "LED20") (pin "1") (pinfunction "A_1") (pintype "passive"))
      (node (ref "R41") (pin "1") (pinfunction "1_1") (pintype "passive"))
    )
    (net (code "57") (name "Net-(LED21-A)") (class "Default")
      (node (ref "LED21") (pin "1") (pinfunction "A_1") (pintype "passive"))
      (node (ref "R43") (pin "1") (pinfunction "1_1") (pintype "passive"))
    )
    (net (code "58") (name "Net-(LED22-A)") (class "Default")
      (node (ref "LED22") (pin "1") (pinfunction "A_1") (pintype "passive"))
      (node (ref "R45") (pin "1") (pinfunction "1_1") (pintype "passive"))
    )
    (net (code "59") (name "Net-(LED23-A)") (class "Default")
      (node (ref "LED23") (pin "1") (pinfunction "A_1") (pintype "passive"))
      (node (ref "R47") (pin "1") (pinfunction "1_1") (pintype "passive"))
    )
    (net (code "60") (name "Net-(LED24-A)") (class "Default")
      (node (ref "LED24") (pin "1") (pinfunction "A_1") (pintype "passive"))
      (node (ref "R49") (pin "1") (pinfunction "1_1") (pintype "passive"))
    )
    (net (code "61") (name "Net-(R27-Pad1)") (class "Default")
      (node (ref "R27") (pin "1") (pinfunction "1_1") (pintype "passive"))
      (node (ref "U3") (pin "A") (pinfunction "A_A") (pintype "passive"))
    )
    (net (code "62") (name "Net-(U3-LED)") (class "Default")
      (node (ref "U3") (pin "2") (pinfunction "LED_2") (pintype "passive"))
      (node (ref "U3") (pin "K") (pinfunction "K_K") (pintype "passive"))
    )
  )
)
